# TP4056.net
KiCad netlist of a schematic drawn in Altium Designer
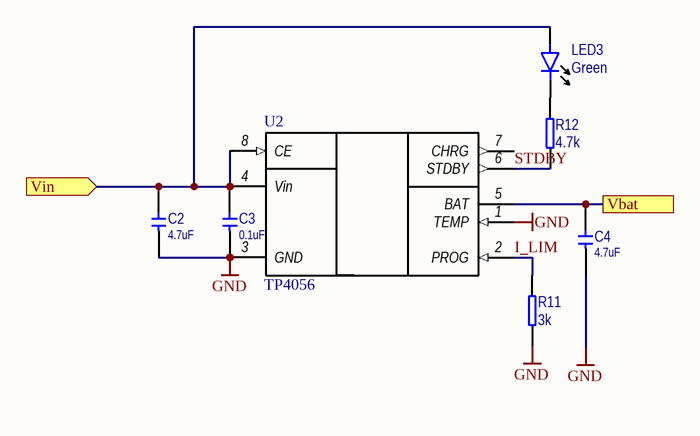
[diagram p0: TP4056.SchDoc]

(export (version "E")
  (design (tool "Eeschema 10.0.6"))
  (components
    (comp (ref "C2")
      (value "4.7uF")
      (footprint "CERCAP 0805")
      (description "Capacitor")
      (fields (field (name "VOLTAGE") "10V") (field (name "Comment") "CERCAP 0805 4.7uF 10V X7R"))
      (libsource (lib "!main") (part "!Capacitor"))
    )
    (comp (ref "C3")
      (value "0.1uF")
      (footprint "CERCAP 0402")
      (description "Capacitor")
      (fields (field (name "VOLTAGE") "10V") (field (name "Comment") "CERCAP 0402 0.1uF 10V X7R"))
      (libsource (lib "!main") (part "!Capacitor"))
    )
    (comp (ref "C4")
      (value "4.7uF")
      (footprint "CERCAP 0805")
      (description "Capacitor")
      (fields (field (name "VOLTAGE") "10V") (field (name "Comment") "CERCAP 0805 4.7uF 10V X7R"))
      (libsource (lib "!main") (part "!Capacitor"))
    )
    (comp (ref "LED3")
      (value "Green")
      (footprint "LED 0603")
      (description "Light Emittering Diode")
      (fields (field (name "Comment") "LED 0603 Green"))
      (libsource (lib "!main") (part "LED"))
    )
    (comp (ref "R11")
      (value "3k")
      (footprint "RES 0402")
      (description "Resistor")
      (fields (field (name "Comment") "RES 0402 3k"))
      (libsource (lib "!main") (part "!Resistor"))
    )
    (comp (ref "R12")
      (value "4.7k")
      (footprint "RES 0402")
      (description "Resistor")
      (fields (field (name "Comment") "RES 0402 4.7k"))
      (libsource (lib "!main") (part "!Resistor"))
    )
    (comp (ref "U2")
      (value "TP4056")
      (footprint "SO-8")
      (description "Charger lin")
      (libsource (lib "power") (part "TP4056"))
    )
  )
  (nets
    (net (code "1") (name "/I_LIM") (class "Default")
      (node (ref "R11") (pin "2") (pinfunction "12_2") (pintype "passive"))
      (node (ref "U2") (pin "2") (pinfunction "PROG_2") (pintype "input"))
    )
    (net (code "2") (name "/STDBY") (class "Default")
      (node (ref "R12") (pin "1") (pinfunction "11_1") (pintype "passive"))
      (node (ref "U2") (pin "6") (pinfunction "STDBY_6") (pintype "output"))
    )
    (net (code "3") (name "/Vbat") (class "Default")
      (node (ref "C4") (pin "2") (pintype "passive"))
      (node (ref "U2") (pin "5") (pinfunction "BAT_5") (pintype "power_in"))
    )
    (net (code "4") (name "/Vin") (class "Default")
      (node (ref "C2") (pin "2") (pintype "passive"))
      (node (ref "C3") (pin "2") (pintype "passive"))
      (node (ref "LED3") (pin "1") (pinfunction "Anode_1") (pintype "passive"))
      (node (ref "U2") (pin "4") (pinfunction "Vin_4") (pintype "power_in"))
      (node (ref "U2") (pin "8") (pinfunction "CE_8") (pintype "input"))
    )
    (net (code "5") (name "GND") (class "Default")
      (node (ref "C2") (pin "1") (pintype "passive"))
      (node (ref "C3") (pin "1") (pintype "passive"))
      (node (ref "C4") (pin "1") (pintype "passive"))
      (node (ref "R11") (pin "1") (pinfunction "11_1") (pintype "passive"))
      (node (ref "U2") (pin "1") (pinfunction "TEMP_1") (pintype "input"))
      (node (ref "U2") (pin "3") (pinfunction "GND_3") (pintype "power_in"))
    )
    (net (code "6") (name "Net-(LED3-Cathode)") (class "Default")
      (node (ref "LED3") (pin "2") (pinfunction "Cathode_2") (pintype "passive"))
      (node (ref "R12") (pin "2") (pinfunction "12_2") (pintype "passive"))
    )
    (net (code "7") (name "unconnected-(U2-CHRG-Pad7)") (class "Default")
      (node (ref "U2") (pin "7") (pinfunction "CHRG_7") (pintype "output"))
    )
  )
)
